# Power_Supply.net
KiCad netlist of a schematic drawn in Altium Designer
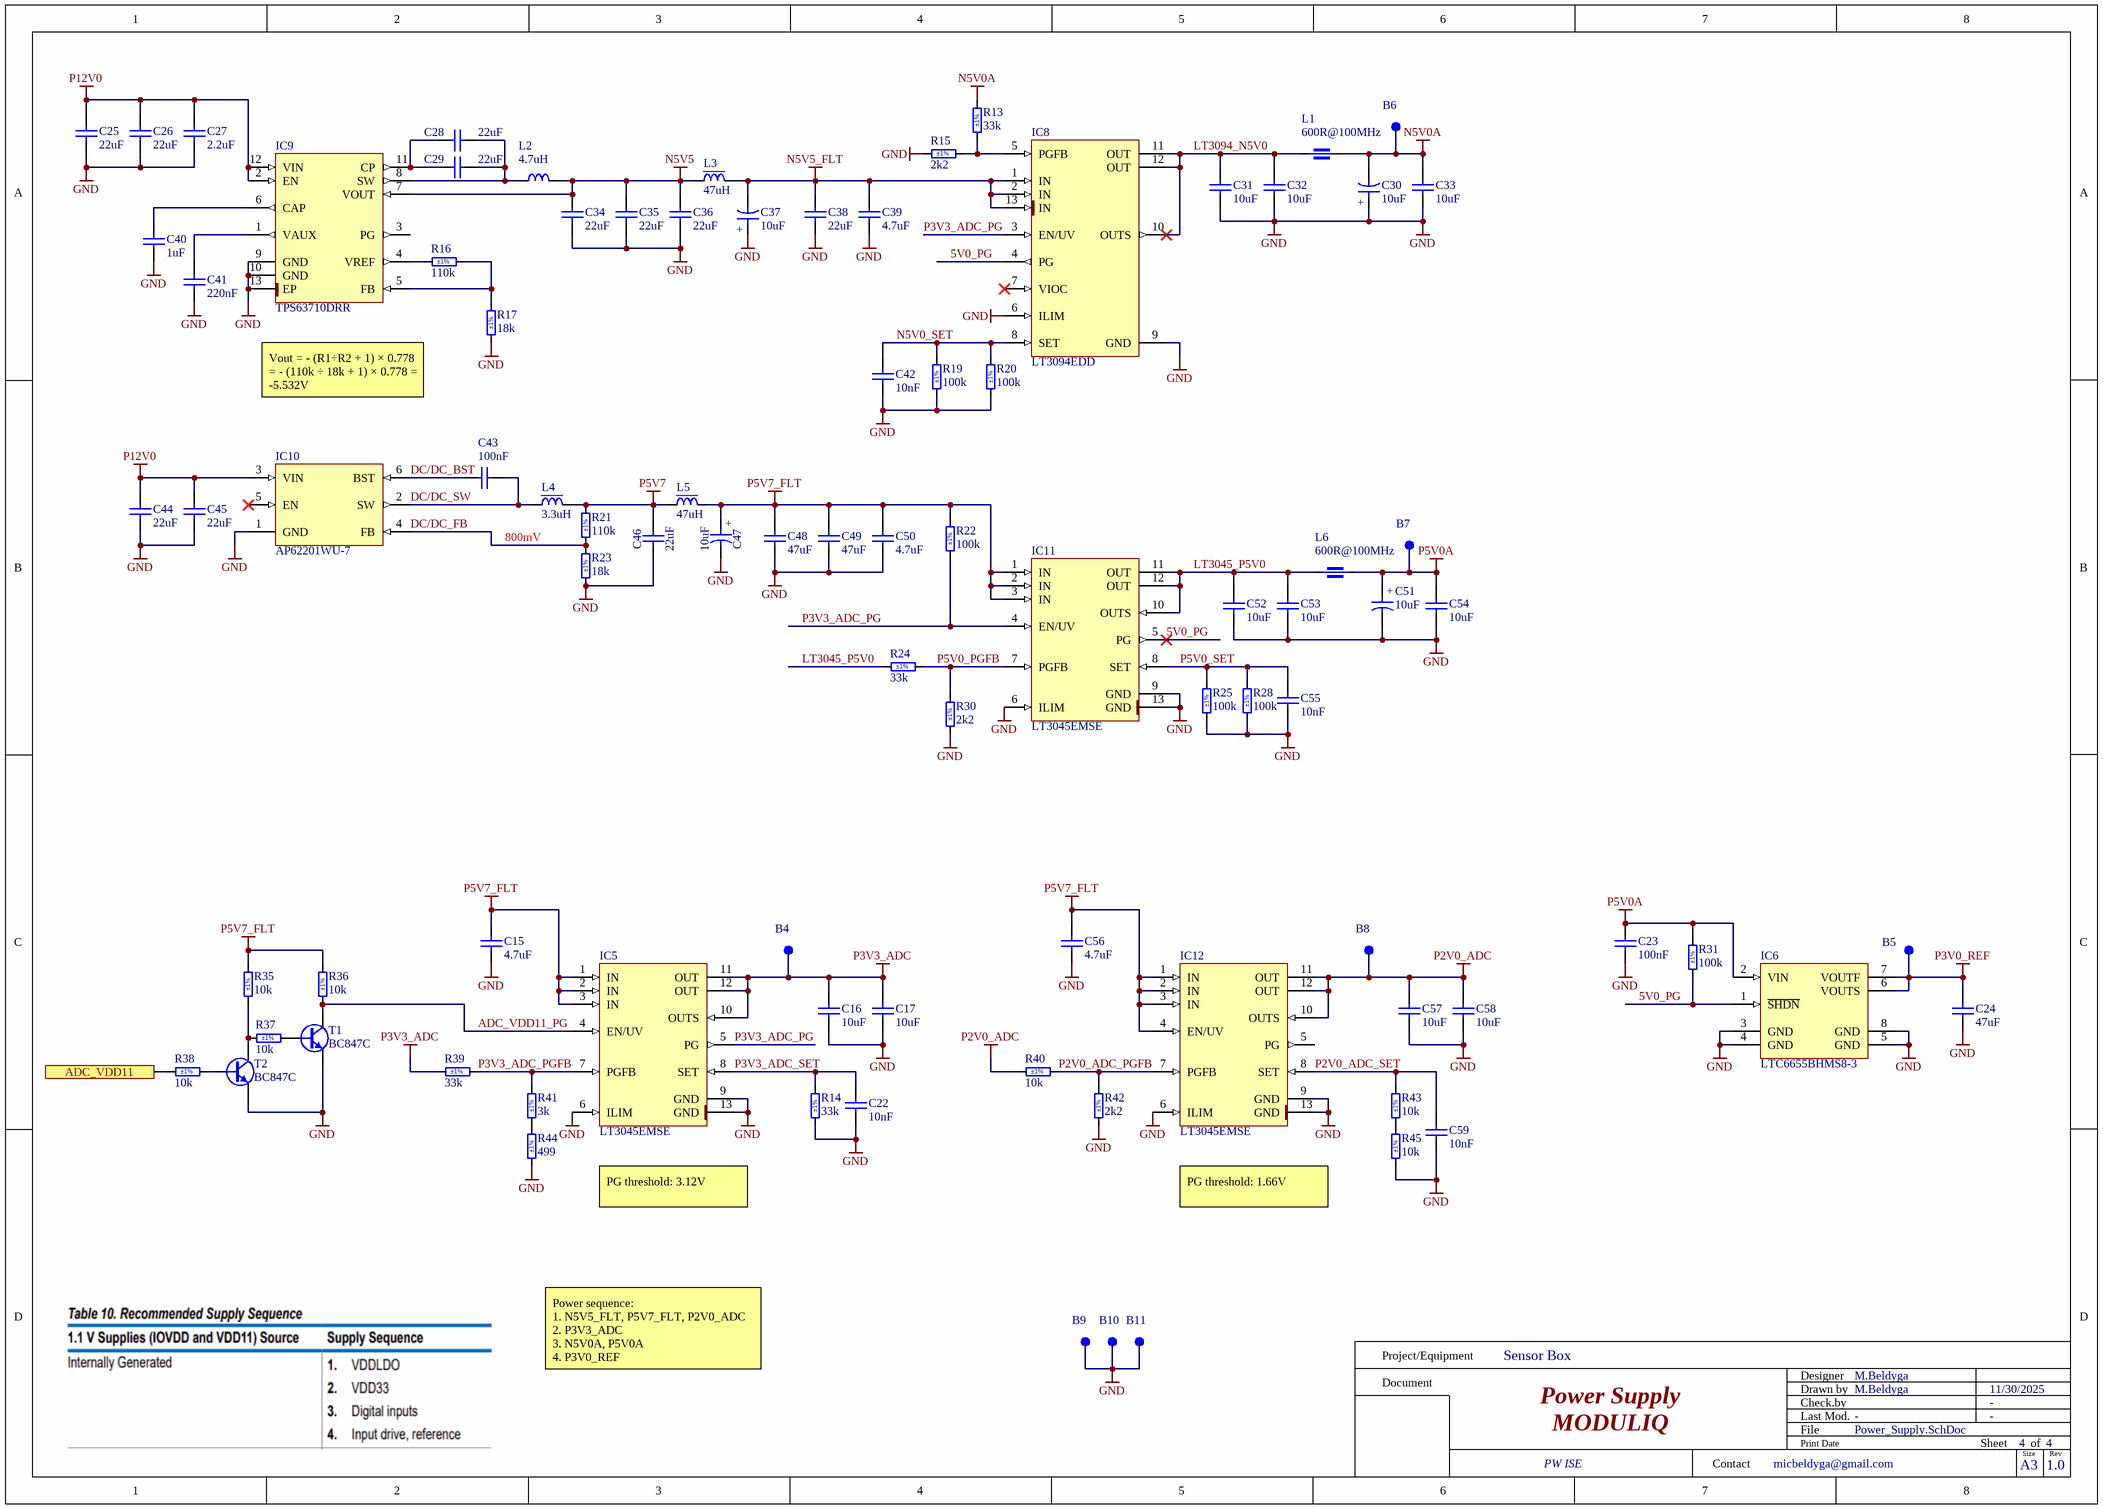
[diagram p0: Power_Supply.SchDoc]

(export (version "E")
  (design (tool "Eeschema 10.0.6"))
  (components
    (comp (ref "B4")
      (value "SMD Pad")
      (footprint "C100")
      (description "Pad")
      (fields (field (name "PART NUMBER") "SMD_PAD_D1MM") (field (name "AUTHOR") "CERN DEM JLC"))
      (libsource (lib "Eletro-mechanical") (part "Single SMD Pad (Round)"))
    )
    (comp (ref "B5")
      (value "SMD Pad")
      (footprint "C100")
      (description "Pad")
      (fields (field (name "PART NUMBER") "SMD_PAD_D1MM") (field (name "AUTHOR") "CERN DEM JLC"))
      (libsource (lib "Eletro-mechanical") (part "Single SMD Pad (Round)"))
    )
    (comp (ref "B6")
      (value "SMD Pad")
      (footprint "C100")
      (description "Pad")
      (fields (field (name "PART NUMBER") "SMD_PAD_D1MM") (field (name "AUTHOR") "CERN DEM JLC"))
      (libsource (lib "Eletro-mechanical") (part "Single SMD Pad (Round)"))
    )
    (comp (ref "B7")
      (value "SMD Pad")
      (footprint "C100")
      (description "Pad")
      (fields (field (name "PART NUMBER") "SMD_PAD_D1MM") (field (name "AUTHOR") "CERN DEM JLC"))
      (libsource (lib "Eletro-mechanical") (part "Single SMD Pad (Round)"))
    )
    (comp (ref "B8")
      (value "SMD Pad")
      (footprint "C100")
      (description "Pad")
      (fields (field (name "PART NUMBER") "SMD_PAD_D1MM") (field (name "AUTHOR") "CERN DEM JLC"))
      (libsource (lib "Eletro-mechanical") (part "Single SMD Pad (Round)"))
    )
    (comp (ref "B9")
      (value "SMD Pad")
      (footprint "C100")
      (description "Pad")
      (fields (field (name "PART NUMBER") "SMD_PAD_D1MM") (field (name "AUTHOR") "CERN DEM JLC"))
      (libsource (lib "Eletro-mechanical") (part "Single SMD Pad (Round)"))
    )
    (comp (ref "B10")
      (value "SMD Pad")
      (footprint "C100")
      (description "Pad")
      (fields (field (name "PART NUMBER") "SMD_PAD_D1MM") (field (name "AUTHOR") "CERN DEM JLC"))
      (libsource (lib "Eletro-mechanical") (part "Single SMD Pad (Round)"))
    )
    (comp (ref "B11")
      (value "SMD Pad")
      (footprint "C100")
      (description "Pad")
      (fields (field (name "PART NUMBER") "SMD_PAD_D1MM") (field (name "AUTHOR") "CERN DEM JLC"))
      (libsource (lib "Eletro-mechanical") (part "Single SMD Pad (Round)"))
    )
    (comp (ref "C15")
      (value "4.7uF")
      (footprint "CAPC1608X90N")
      (description "Non-polarised capacitor")
      (fields
        (field (name "PART NUMBER") "CC0603_4.7UF_25V_10%_X5R")
        (field (name "VOLTAGE") "25V")
        (field (name "AUTHOR") "CERN DEM JLC")
      )
      (libsource (lib "Capacitors") (part "Capacitor - non polarized"))
    )
    (comp (ref "C16")
      (value "10uF")
      (footprint "CAPC2012X95N")
      (description "Non-polarised capacitor")
      (fields
        (field (name "PART NUMBER") "CC0805_10UF_25V_10%_X5R")
        (field (name "VOLTAGE") "25V")
        (field (name "AUTHOR") "CERN DEM JLC")
      )
      (libsource (lib "Capacitors") (part "Capacitor - non polarized"))
    )
    (comp (ref "C17")
      (value "10uF")
      (footprint "CAPC2012X95N")
      (description "Non-polarised capacitor")
      (fields
        (field (name "PART NUMBER") "CC0805_10UF_25V_10%_X5R")
        (field (name "VOLTAGE") "25V")
        (field (name "AUTHOR") "CERN DEM JLC")
      )
      (libsource (lib "Capacitors") (part "Capacitor - non polarized"))
    )
    (comp (ref "C22")
      (value "10nF")
      (footprint "CAPC1005X55N")
      (description "Non-polarised capacitor")
      (fields
        (field (name "PART NUMBER") "CC0402_10NF_16V_10%_X7R")
        (field (name "VOLTAGE") "16V")
        (field (name "AUTHOR") "CERN DEM JLC")
      )
      (libsource (lib "Capacitors") (part "Capacitor - non polarized"))
    )
    (comp (ref "C23")
      (value "100nF")
      (footprint "CAPC1005X55N")
      (description "Non-polarised capacitor")
      (fields
        (field (name "PART NUMBER") "CC0402_100NF_50V_10%_X7R")
        (field (name "VOLTAGE") "50V")
        (field (name "AUTHOR") "CERN DEM MR")
      )
      (libsource (lib "Capacitors") (part "Capacitor - non polarized"))
    )
    (comp (ref "C24")
      (value "47uF")
      (footprint "CAPC2012X140N")
      (description "Non-polarised capacitor")
      (fields
        (field (name "PART NUMBER") "CC0805_47UF_6.3V_10%_X5R")
        (field (name "VOLTAGE") "6.3V")
        (field (name "AUTHOR") "CERN DEM HF")
      )
      (libsource (lib "Capacitors") (part "Capacitor - non polarized"))
    )
    (comp (ref "C25")
      (value "22uF")
      (footprint "CAPC2012X135N")
      (description "Non-polarised capacitor")
      (fields
        (field (name "PART NUMBER") "CC0805_22UF_16V_10%_X5R")
        (field (name "VOLTAGE") "16V")
        (field (name "AUTHOR") "CERN DEM JLC")
      )
      (libsource (lib "Capacitors") (part "Capacitor - non polarized"))
    )
    (comp (ref "C26")
      (value "22uF")
      (footprint "CAPC2012X135N")
      (description "Non-polarised capacitor")
      (fields
        (field (name "PART NUMBER") "CC0805_22UF_16V_10%_X5R")
        (field (name "VOLTAGE") "16V")
        (field (name "AUTHOR") "CERN DEM JLC")
      )
      (libsource (lib "Capacitors") (part "Capacitor - non polarized"))
    )
    (comp (ref "C27")
      (value "2.2uF")
      (footprint "CAPC1005X55N")
      (description "Non-polarised capacitor")
      (fields
        (field (name "PART NUMBER") "CC0402_2.2UF_25V_10%_X5R")
        (field (name "VOLTAGE") "25V")
        (field (name "AUTHOR") "CERN DEM BC")
      )
      (libsource (lib "Capacitors") (part "Capacitor - non polarized"))
    )
    (comp (ref "C28")
      (value "22uF")
      (footprint "CAPC2012X135N")
      (description "Non-polarised capacitor")
      (fields
        (field (name "PART NUMBER") "CC0805_22UF_16V_10%_X5R")
        (field (name "VOLTAGE") "16V")
        (field (name "AUTHOR") "CERN DEM JLC")
      )
      (libsource (lib "Capacitors") (part "Capacitor - non polarized"))
    )
    (comp (ref "C29")
      (value "22uF")
      (footprint "CAPC2012X135N")
      (description "Non-polarised capacitor")
      (fields
        (field (name "PART NUMBER") "CC0805_22UF_16V_10%_X5R")
        (field (name "VOLTAGE") "16V")
        (field (name "AUTHOR") "CERN DEM JLC")
      )
      (libsource (lib "Capacitors") (part "Capacitor - non polarized"))
    )
    (comp (ref "C30")
      (value "10uF")
      (footprint "CAPMP3216X180N")
      (description "Polarised capacitor")
      (fields
        (field (name "PART NUMBER") "CTE3216-18_10UF_10V_10%_LESR1800")
        (field (name "VOLTAGE") "10V")
        (field (name "AUTHOR") "CERN DEM JLC")
      )
      (libsource (lib "Capacitors") (part "Capacitor - polarized"))
    )
    (comp (ref "C31")
      (value "10uF")
      (footprint "CAPC2012X95N")
      (description "Non-polarised capacitor")
      (fields
        (field (name "PART NUMBER") "CC0805_10UF_25V_10%_X5R")
        (field (name "VOLTAGE") "25V")
        (field (name "AUTHOR") "CERN DEM JLC")
      )
      (libsource (lib "Capacitors") (part "Capacitor - non polarized"))
    )
    (comp (ref "C32")
      (value "10uF")
      (footprint "CAPC2012X95N")
      (description "Non-polarised capacitor")
      (fields
        (field (name "PART NUMBER") "CC0805_10UF_25V_10%_X5R")
        (field (name "VOLTAGE") "25V")
        (field (name "AUTHOR") "CERN DEM JLC")
      )
      (libsource (lib "Capacitors") (part "Capacitor - non polarized"))
    )
    (comp (ref "C33")
      (value "10uF")
      (footprint "CAPC2012X95N")
      (description "Non-polarised capacitor")
      (fields
        (field (name "PART NUMBER") "CC0805_10UF_25V_10%_X5R")
        (field (name "VOLTAGE") "25V")
        (field (name "AUTHOR") "CERN DEM JLC")
      )
      (libsource (lib "Capacitors") (part "Capacitor - non polarized"))
    )
    (comp (ref "C34")
      (value "22uF")
      (footprint "CAPC2012X135N")
      (description "Non-polarised capacitor")
      (fields
        (field (name "PART NUMBER") "CC0805_22UF_16V_10%_X5R")
        (field (name "VOLTAGE") "16V")
        (field (name "AUTHOR") "CERN DEM JLC")
      )
      (libsource (lib "Capacitors") (part "Capacitor - non polarized"))
    )
    (comp (ref "C35")
      (value "22uF")
      (footprint "CAPC2012X135N")
      (description "Non-polarised capacitor")
      (fields
        (field (name "PART NUMBER") "CC0805_22UF_16V_10%_X5R")
        (field (name "VOLTAGE") "16V")
        (field (name "AUTHOR") "CERN DEM JLC")
      )
      (libsource (lib "Capacitors") (part "Capacitor - non polarized"))
    )
    (comp (ref "C36")
      (value "22uF")
      (footprint "CAPC2012X135N")
      (description "Non-polarised capacitor")
      (fields
        (field (name "PART NUMBER") "CC0805_22UF_16V_10%_X5R")
        (field (name "VOLTAGE") "16V")
        (field (name "AUTHOR") "CERN DEM JLC")
      )
      (libsource (lib "Capacitors") (part "Capacitor - non polarized"))
    )
    (comp (ref "C37")
      (value "10uF")
      (footprint "CAPMP3216X180N")
      (description "Polarised capacitor")
      (fields
        (field (name "PART NUMBER") "CTE3216-18_10UF_16V_20%_AVX_TCJ")
        (field (name "VOLTAGE") "16V")
        (field (name "AUTHOR") "CERN DEM JLC")
      )
      (libsource (lib "Capacitors") (part "Capacitor - polarized"))
    )
    (comp (ref "C38")
      (value "22uF")
      (footprint "CAPC2012X135N")
      (description "Non-polarised capacitor")
      (fields
        (field (name "PART NUMBER") "CC0805_22UF_16V_10%_X5R")
        (field (name "VOLTAGE") "16V")
        (field (name "AUTHOR") "CERN DEM JLC")
      )
      (libsource (lib "Capacitors") (part "Capacitor - non polarized"))
    )
    (comp (ref "C39")
      (value "4.7uF")
      (footprint "CAPC1608X90N")
      (description "Non-polarised capacitor")
      (fields
        (field (name "PART NUMBER") "CC0603_4.7UF_25V_10%_X5R")
        (field (name "VOLTAGE") "25V")
        (field (name "AUTHOR") "CERN DEM JLC")
      )
      (libsource (lib "Capacitors") (part "Capacitor - non polarized"))
    )
    (comp (ref "C40")
      (value "1uF")
      (footprint "CAPC1005X55N")
      (description "Non-polarised capacitor")
      (fields
        (field (name "PART NUMBER") "CC0402_1UF_16V_10%_X5R")
        (field (name "VOLTAGE") "16V")
        (field (name "AUTHOR") "CERN DEM JLC")
      )
      (libsource (lib "Capacitors") (part "Capacitor - non polarized"))
    )
    (comp (ref "C41")
      (value "220nF")
      (footprint "CAPC1005X55N")
      (description "Non-polarised capacitor")
      (fields
        (field (name "PART NUMBER") "CC0402_220NF_25V_10%_X7R")
        (field (name "VOLTAGE") "25V")
        (field (name "AUTHOR") "CERN DEM BC")
      )
      (libsource (lib "Capacitors") (part "Capacitor - non polarized"))
    )
    (comp (ref "C42")
      (value "10nF")
      (footprint "CAPC1005X55N")
      (description "Non-polarised capacitor")
      (fields
        (field (name "PART NUMBER") "CC0402_10NF_16V_10%_X7R")
        (field (name "VOLTAGE") "16V")
        (field (name "AUTHOR") "CERN DEM JLC")
      )
      (libsource (lib "Capacitors") (part "Capacitor - non polarized"))
    )
    (comp (ref "C43")
      (value "100nF")
      (footprint "CAPC1005X55N")
      (description "Non-polarised capacitor")
      (fields
        (field (name "PART NUMBER") "CC0402_100NF_16V_10%_X7R")
        (field (name "VOLTAGE") "16V")
        (field (name "AUTHOR") "CERN DEM JLC")
      )
      (libsource (lib "Capacitors") (part "Capacitor - non polarized"))
    )
    (comp (ref "C44")
      (value "22uF")
      (footprint "CAPC2012X135N")
      (description "Non-polarised capacitor")
      (fields
        (field (name "PART NUMBER") "CC0805_22UF_16V_10%_X5R")
        (field (name "VOLTAGE") "16V")
        (field (name "AUTHOR") "CERN DEM JLC")
      )
      (libsource (lib "Capacitors") (part "Capacitor - non polarized"))
    )
    (comp (ref "C45")
      (value "22uF")
      (footprint "CAPC2012X135N")
      (description "Non-polarised capacitor")
      (fields
        (field (name "PART NUMBER") "CC0805_22UF_16V_10%_X5R")
        (field (name "VOLTAGE") "16V")
        (field (name "AUTHOR") "CERN DEM JLC")
      )
      (libsource (lib "Capacitors") (part "Capacitor - non polarized"))
    )
    (comp (ref "C46")
      (value "22uF")
      (footprint "CAPC2012X135N")
      (description "Non-polarised capacitor")
      (fields
        (field (name "PART NUMBER") "CC0805_22UF_16V_10%_X5R")
        (field (name "VOLTAGE") "16V")
        (field (name "AUTHOR") "CERN DEM JLC")
      )
      (libsource (lib "Capacitors") (part "Capacitor - non polarized"))
    )
    (comp (ref "C47")
      (value "10uF")
      (footprint "CAPMP3216X180N")
      (description "Polarised capacitor")
      (fields
        (field (name "PART NUMBER") "CTE3216-18_10UF_16V_20%_AVX_TCJ")
        (field (name "VOLTAGE") "16V")
        (field (name "AUTHOR") "CERN DEM JLC")
      )
      (libsource (lib "Capacitors") (part "Capacitor - polarized"))
    )
    (comp (ref "C48")
      (value "47uF")
      (footprint "CAPC3216X180N")
      (description "Non-polarised capacitor")
      (fields
        (field (name "PART NUMBER") "CC1206_47UF_25V_20%_X5R")
        (field (name "VOLTAGE") "25V")
        (field (name "AUTHOR") "CERN DEM JLC")
      )
      (libsource (lib "Capacitors") (part "Capacitor - non polarized"))
    )
    (comp (ref "C49")
      (value "47uF")
      (footprint "CAPC3216X180N")
      (description "Non-polarised capacitor")
      (fields
        (field (name "PART NUMBER") "CC1206_47UF_25V_20%_X5R")
        (field (name "VOLTAGE") "25V")
        (field (name "AUTHOR") "CERN DEM JLC")
      )
      (libsource (lib "Capacitors") (part "Capacitor - non polarized"))
    )
    (comp (ref "C50")
      (value "4.7uF")
      (footprint "CAPC1608X90N")
      (description "Non-polarised capacitor")
      (fields
        (field (name "PART NUMBER") "CC0603_4.7UF_25V_10%_X5R")
        (field (name "VOLTAGE") "25V")
        (field (name "AUTHOR") "CERN DEM JLC")
      )
      (libsource (lib "Capacitors") (part "Capacitor - non polarized"))
    )
    (comp (ref "C51")
      (value "10uF")
      (footprint "CAPMP3216X180N")
      (description "Polarised capacitor")
      (fields
        (field (name "PART NUMBER") "CTE3216-18_10UF_10V_10%_LESR1800")
        (field (name "VOLTAGE") "10V")
        (field (name "AUTHOR") "CERN DEM JLC")
      )
      (libsource (lib "Capacitors") (part "Capacitor - polarized"))
    )
    (comp (ref "C52")
      (value "10uF")
      (footprint "CAPC2012X95N")
      (description "Non-polarised capacitor")
      (fields
        (field (name "PART NUMBER") "CC0805_10UF_25V_10%_X5R")
        (field (name "VOLTAGE") "25V")
        (field (name "AUTHOR") "CERN DEM JLC")
      )
      (libsource (lib "Capacitors") (part "Capacitor - non polarized"))
    )
    (comp (ref "C53")
      (value "10uF")
      (footprint "CAPC2012X95N")
      (description "Non-polarised capacitor")
      (fields
        (field (name "PART NUMBER") "CC0805_10UF_25V_10%_X5R")
        (field (name "VOLTAGE") "25V")
        (field (name "AUTHOR") "CERN DEM JLC")
      )
      (libsource (lib "Capacitors") (part "Capacitor - non polarized"))
    )
    (comp (ref "C54")
      (value "10uF")
      (footprint "CAPC2012X95N")
      (description "Non-polarised capacitor")
      (fields
        (field (name "PART NUMBER") "CC0805_10UF_25V_10%_X5R")
        (field (name "VOLTAGE") "25V")
        (field (name "AUTHOR") "CERN DEM JLC")
      )
      (libsource (lib "Capacitors") (part "Capacitor - non polarized"))
    )
    (comp (ref "C55")
      (value "10nF")
      (footprint "CAPC1005X55N")
      (description "Non-polarised capacitor")
      (fields
        (field (name "PART NUMBER") "CC0402_10NF_16V_10%_X7R")
        (field (name "VOLTAGE") "16V")
        (field (name "AUTHOR") "CERN DEM JLC")
      )
      (libsource (lib "Capacitors") (part "Capacitor - non polarized"))
    )
    (comp (ref "C56")
      (value "4.7uF")
      (footprint "CAPC1608X90N")
      (description "Non-polarised capacitor")
      (fields
        (field (name "PART NUMBER") "CC0603_4.7UF_25V_10%_X5R")
        (field (name "VOLTAGE") "25V")
        (field (name "AUTHOR") "CERN DEM JLC")
      )
      (libsource (lib "Capacitors") (part "Capacitor - non polarized"))
    )
    (comp (ref "C57")
      (value "10uF")
      (footprint "CAPC2012X95N")
      (description "Non-polarised capacitor")
      (fields
        (field (name "PART NUMBER") "CC0805_10UF_25V_10%_X5R")
        (field (name "VOLTAGE") "25V")
        (field (name "AUTHOR") "CERN DEM JLC")
      )
      (libsource (lib "Capacitors") (part "Capacitor - non polarized"))
    )
    (comp (ref "C58")
      (value "10uF")
      (footprint "CAPC2012X95N")
      (description "Non-polarised capacitor")
      (fields
        (field (name "PART NUMBER") "CC0805_10UF_25V_10%_X5R")
        (field (name "VOLTAGE") "25V")
        (field (name "AUTHOR") "CERN DEM JLC")
      )
      (libsource (lib "Capacitors") (part "Capacitor - non polarized"))
    )
    (comp (ref "C59")
      (value "10nF")
      (footprint "CAPC1005X55N")
      (description "Non-polarised capacitor")
      (fields
        (field (name "PART NUMBER") "CC0402_10NF_16V_10%_X7R")
        (field (name "VOLTAGE") "16V")
        (field (name "AUTHOR") "CERN DEM JLC")
      )
      (libsource (lib "Capacitors") (part "Capacitor - non polarized"))
    )
    (comp (ref "IC5")
      (value "LT3045EMSE")
      (footprint "SOP65P490X110-13N-R175X294")
      (description "20V, 500mA, Ultralow Noise, Ultrahigh PSRR Linear Regulator")
      (fields (field (name "MANUFACTURER") "LINEAR TECHNOLOGY") (field (name "AUTHOR") "CERN DEM HF"))
      (libsource (lib "ICs And Semiconductors") (part "LT3045"))
    )
    (comp (ref "IC6")
      (value "LTC6655BHMS8-3")
      (footprint "SOP65P490X110-8N")
      (description "0.25ppm Noise, Low Drift Precision Buffered Voltage Reference")
      (fields (field (name "MANUFACTURER") "ANALOG DEVICES") (field (name "AUTHOR") "CERN DEM HF"))
      (libsource (lib "ICs And Semiconductors") (part "LTC6655"))
    )
    (comp (ref "IC8")
      (value "LT3094EDD")
      (footprint "SON45P300X300X80-13N-R175X248")
      (description "-20V, 500mA, Ultralow Noise, Ultrahigh PSRR Negative Linear Regulator")
      (fields
        (field (name "PART NUMBER") "LT3094EDD#PBF")
        (field (name "MANUFACTURER") "LINEAR TECHNOLOGY")
        (field (name "AUTHOR") "CERN DEM JLC")
      )
      (libsource (lib "ICs And Semiconductors") (part "LT3094"))
    )
    (comp (ref "IC9")
      (value "TPS63710DRR")
      (footprint "SON50P300X300X80-13N-R160X260")
      (description "-1 to -5.5VDC, 1A Output, Low Noise Synchronous Inverting Buck Converter")
      (fields (field (name "MANUFACTURER") "TEXAS INSTRUMENTS") (field (name "AUTHOR") "CERN DEM BC"))
      (libsource (lib "ICs And Semiconductors") (part "TPS63710"))
    )
    (comp (ref "IC10")
      (value "AP62201WU-7")
      (footprint "SOT95P280X100-6N")
      (description "4.2V TO 18V INPUT, 2A LOW IQ SYNCHRONOUS BUCK CONVERTER")
      (fields
        (field (name "MANUFACTURER") "DIODES INCORPORATED")
        (field (name "MANUFACTURER PART NUMBER") "AP62201WU")
        (field (name "AUTHOR") "CERN DEM HF")
      )
      (libsource (lib "ICs And Semiconductors") (part "AP62201WU"))
    )
    (comp (ref "IC11")
      (value "LT3045EMSE")
      (footprint "SOP65P490X110-13N-R175X294")
      (description "20V, 500mA, Ultralow Noise, Ultrahigh PSRR Linear Regulator")
      (fields (field (name "MANUFACTURER") "LINEAR TECHNOLOGY") (field (name "AUTHOR") "CERN DEM HF"))
      (libsource (lib "ICs And Semiconductors") (part "LT3045"))
    )
    (comp (ref "IC12")
      (value "LT3045EMSE")
      (footprint "SOP65P490X110-13N-R175X294")
      (description "20V, 500mA, Ultralow Noise, Ultrahigh PSRR Linear Regulator")
      (fields (field (name "MANUFACTURER") "LINEAR TECHNOLOGY") (field (name "AUTHOR") "CERN DEM HF"))
      (libsource (lib "ICs And Semiconductors") (part "LT3045"))
    )
    (comp (ref "L1")
      (value "600R@100MHz")
      (footprint "INDC1608X95N")
      (fields
        (field (name "PART NUMBER") "IND0603_MURATA_BLM18BD601SN1D")
        (field (name "POWER") "200mA")
        (field (name "TOLERANCE") "±25%")
        (field (name "AUTHOR") "CERN DEM JLC")
      )
      (libsource (lib "Inductors & Transformers") (part "Ferrite Bead"))
    )
    (comp (ref "L2")
      (value "4.7uH")
      (footprint "IND_COILCRAFT_EPL3015")
      (description "Inductor")
      (fields
        (field (name "PART NUMBER") "IND_4.7UH_20%_COILCRAFT_EPL3015")
        (field (name "POWER") "1A")
        (field (name "AUTHOR") "CERN DEM BC")
      )
      (libsource (lib "Inductors & Transformers") (part "Inductor"))
    )
    (comp (ref "L3")
      (value "47uH")
      (footprint "IND_WURTH_WE-LHMI_7050")
      (description "Inductor With Core")
      (fields
        (field (name "PART NUMBER") "IND_47UH_20%_WURTH_WE-LHMI_74437349470")
        (field (name "POWER") "1.45A")
        (field (name "AUTHOR") "CERN DEM HF")
      )
      (libsource (lib "Inductors & Transformers") (part "Inductor With Magnetic core"))
    )
    (comp (ref "L4")
      (value "3.3uH")
      (footprint "IND_COILCRAFT_SD43")
      (description "Inductor With Core")
      (fields
        (field (name "PART NUMBER") "IND_3.3UH_20%_COILCRAFT_SD43-332MLB")
        (field (name "POWER") "2.1A")
        (field (name "AUTHOR") "CERN DEM JLC")
      )
      (libsource (lib "Inductors & Transformers") (part "Inductor With Magnetic core"))
    )
    (comp (ref "L5")
      (value "47uH")
      (footprint "IND_WURTH_WE-LHMI_7050")
      (description "Inductor With Core")
      (fields
        (field (name "PART NUMBER") "IND_47UH_20%_WURTH_WE-LHMI_74437349470")
        (field (name "POWER") "1.45A")
        (field (name "AUTHOR") "CERN DEM HF")
      )
      (libsource (lib "Inductors & Transformers") (part "Inductor With Magnetic core"))
    )
    (comp (ref "L6")
      (value "600R@100MHz")
      (footprint "INDC1608X95N")
      (fields
        (field (name "PART NUMBER") "IND0603_MURATA_BLM18BD601SN1D")
        (field (name "POWER") "200mA")
        (field (name "TOLERANCE") "±25%")
        (field (name "AUTHOR") "CERN DEM JLC")
      )
      (libsource (lib "Inductors & Transformers") (part "Ferrite Bead"))
    )
    (comp (ref "R13")
      (value "33k")
      (footprint "RESC1005X40N")
      (description "Resistor - 1%")
      (fields
        (field (name "TOLERANCE") "±1%")
        (field (name "PART NUMBER") "R0402_33K_1%_0.0625W_100PPM")
        (field (name "POWER") "0.0625W")
        (field (name "AUTHOR") "CERN DEM JLC")
      )
      (libsource (lib "Resistors") (part "Resistor - 1%"))
    )
    (comp (ref "R14")
      (value "33k")
      (footprint "RESC1005X40N")
      (description "Resistor - 1%")
      (fields
        (field (name "TOLERANCE") "±1%")
        (field (name "PART NUMBER") "R0402_33K_1%_0.0625W_100PPM")
        (field (name "POWER") "0.0625W")
        (field (name "AUTHOR") "CERN DEM JLC")
      )
      (libsource (lib "Resistors") (part "Resistor - 1%"))
    )
    (comp (ref "R15")
      (value "2k2")
      (footprint "RESC1005X40N")
      (description "Resistor - 1%")
      (fields
        (field (name "TOLERANCE") "±1%")
        (field (name "PART NUMBER") "R0402_2K2_1%_0.0625W_100PPM")
        (field (name "POWER") "0.0625W")
        (field (name "AUTHOR") "CERN DEM JLC")
      )
      (libsource (lib "Resistors") (part "Resistor - 1%"))
    )
    (comp (ref "R16")
      (value "110k")
      (footprint "RESC1005X40N")
      (description "Resistor - 1%")
      (fields
        (field (name "TOLERANCE") "±1%")
        (field (name "PART NUMBER") "R0402_110K_1%_0.0625W_100PPM")
        (field (name "POWER") "0.0625W")
        (field (name "AUTHOR") "CERN DEM JLC")
      )
      (libsource (lib "Resistors") (part "Resistor - 1%"))
    )
    (comp (ref "R17")
      (value "18k")
      (footprint "RESC1005X40N")
      (description "Resistor - 1%")
      (fields
        (field (name "TOLERANCE") "±1%")
        (field (name "PART NUMBER") "R0402_18K_1%_0.0625W_100PPM")
        (field (name "POWER") "0.0625W")
        (field (name "AUTHOR") "CERN DEM JLC")
      )
      (libsource (lib "Resistors") (part "Resistor - 1%"))
    )
    (comp (ref "R19")
      (value "100k")
      (footprint "RESC1005X40N")
      (description "Resistor - 1%")
      (fields
        (field (name "TOLERANCE") "±1%")
        (field (name "PART NUMBER") "R0402_100K_1%_0.0625W_100PPM")
        (field (name "POWER") "0.0625W")
        (field (name "AUTHOR") "CERN DEM JLC")
      )
      (libsource (lib "Resistors") (part "Resistor - 1%"))
    )
    (comp (ref "R20")
      (value "100k")
      (footprint "RESC1005X40N")
      (description "Resistor - 1%")
      (fields
        (field (name "TOLERANCE") "±1%")
        (field (name "PART NUMBER") "R0402_100K_1%_0.0625W_100PPM")
        (field (name "POWER") "0.0625W")
        (field (name "AUTHOR") "CERN DEM JLC")
      )
      (libsource (lib "Resistors") (part "Resistor - 1%"))
    )
    (comp (ref "R21")
      (value "110k")
      (footprint "RESC1005X40N")
      (description "Resistor - 1%")
      (fields
        (field (name "TOLERANCE") "±1%")
        (field (name "PART NUMBER") "R0402_110K_1%_0.0625W_100PPM")
        (field (name "POWER") "0.0625W")
        (field (name "AUTHOR") "CERN DEM JLC")
      )
      (libsource (lib "Resistors") (part "Resistor - 1%"))
    )
    (comp (ref "R22")
      (value "100k")
      (footprint "RESC1005X40N")
      (description "Resistor - 1%")
      (fields
        (field (name "TOLERANCE") "±1%")
        (field (name "PART NUMBER") "R0402_100K_1%_0.0625W_100PPM")
        (field (name "POWER") "0.0625W")
        (field (name "AUTHOR") "CERN DEM JLC")
      )
      (libsource (lib "Resistors") (part "Resistor - 1%"))
    )
    (comp (ref "R23")
      (value "18k")
      (footprint "RESC1005X40N")
      (description "Resistor - 1%")
      (fields
        (field (name "TOLERANCE") "±1%")
        (field (name "PART NUMBER") "R0402_18K_1%_0.0625W_100PPM")
        (field (name "POWER") "0.0625W")
        (field (name "AUTHOR") "CERN DEM JLC")
      )
      (libsource (lib "Resistors") (part "Resistor - 1%"))
    )
    (comp (ref "R24")
      (value "33k")
      (footprint "RESC1005X40N")
      (description "Resistor - 1%")
      (fields
        (field (name "TOLERANCE") "±1%")
        (field (name "PART NUMBER") "R0402_33K_1%_0.0625W_100PPM")
        (field (name "POWER") "0.0625W")
        (field (name "AUTHOR") "CERN DEM JLC")
      )
      (libsource (lib "Resistors") (part "Resistor - 1%"))
    )
    (comp (ref "R25")
      (value "100k")
      (footprint "RESC1005X40N")
      (description "Resistor - 1%")
      (fields
        (field (name "TOLERANCE") "±1%")
        (field (name "PART NUMBER") "R0402_100K_1%_0.0625W_100PPM")
        (field (name "POWER") "0.0625W")
        (field (name "AUTHOR") "CERN DEM JLC")
      )
      (libsource (lib "Resistors") (part "Resistor - 1%"))
    )
    (comp (ref "R28")
      (value "100k")
      (footprint "RESC1005X40N")
      (description "Resistor - 1%")
      (fields
        (field (name "TOLERANCE") "±1%")
        (field (name "PART NUMBER") "R0402_100K_1%_0.0625W_100PPM")
        (field (name "POWER") "0.0625W")
        (field (name "AUTHOR") "CERN DEM JLC")
      )
      (libsource (lib "Resistors") (part "Resistor - 1%"))
    )
    (comp (ref "R30")
      (value "2k2")
      (footprint "RESC1005X40N")
      (description "Resistor - 1%")
      (fields
        (field (name "TOLERANCE") "±1%")
        (field (name "PART NUMBER") "R0402_2K2_1%_0.0625W_100PPM")
        (field (name "POWER") "0.0625W")
        (field (name "AUTHOR") "CERN DEM JLC")
      )
      (libsource (lib "Resistors") (part "Resistor - 1%"))
    )
    (comp (ref "R31")
      (value "100k")
      (footprint "RESC1005X40N")
      (description "Resistor - 1%")
      (fields
        (field (name "TOLERANCE") "±1%")
        (field (name "PART NUMBER") "R0402_100K_1%_0.0625W_100PPM")
        (field (name "POWER") "0.0625W")
        (field (name "AUTHOR") "CERN DEM JLC")
      )
      (libsource (lib "Resistors") (part "Resistor - 1%"))
    )
    (comp (ref "R35")
      (value "10k")
      (footprint "RESC1005X40N")
      (description "Resistor - 1%")
      (fields
        (field (name "TOLERANCE") "±1%")
        (field (name "PART NUMBER") "R0402_10K_1%_0.0625W_100PPM")
        (field (name "POWER") "0.0625W")
        (field (name "AUTHOR") "CERN DEM JLC")
      )
      (libsource (lib "Resistors") (part "Resistor - 1%"))
    )
    (comp (ref "R36")
      (value "10k")
      (footprint "RESC1005X40N")
      (description "Resistor - 1%")
      (fields
        (field (name "TOLERANCE") "±1%")
        (field (name "PART NUMBER") "R0402_10K_1%_0.0625W_100PPM")
        (field (name "POWER") "0.0625W")
        (field (name "AUTHOR") "CERN DEM JLC")
      )
      (libsource (lib "Resistors") (part "Resistor - 1%"))
    )
    (comp (ref "R37")
      (value "10k")
      (footprint "RESC1005X40N")
      (description "Resistor - 1%")
      (fields
        (field (name "TOLERANCE") "±1%")
        (field (name "PART NUMBER") "R0402_10K_1%_0.0625W_100PPM")
        (field (name "POWER") "0.0625W")
        (field (name "AUTHOR") "CERN DEM JLC")
      )
      (libsource (lib "Resistors") (part "Resistor - 1%"))
    )
    (comp (ref "R38")
      (value "10k")
      (footprint "RESC1005X40N")
      (description "Resistor - 1%")
      (fields
        (field (name "TOLERANCE") "±1%")
        (field (name "PART NUMBER") "R0402_10K_1%_0.0625W_100PPM")
        (field (name "POWER") "0.0625W")
        (field (name "AUTHOR") "CERN DEM JLC")
      )
      (libsource (lib "Resistors") (part "Resistor - 1%"))
    )
    (comp (ref "R39")
      (value "33k")
      (footprint "RESC1005X40N")
      (description "Resistor - 1%")
      (fields
        (field (name "TOLERANCE") "±1%")
        (field (name "PART NUMBER") "R0402_33K_1%_0.0625W_100PPM")
        (field (name "POWER") "0.0625W")
        (field (name "AUTHOR") "CERN DEM JLC")
      )
      (libsource (lib "Resistors") (part "Resistor - 1%"))
    )
    (comp (ref "R40")
      (value "10k")
      (footprint "RESC1005X40N")
      (description "Resistor - 1%")
      (fields
        (field (name "TOLERANCE") "±1%")
        (field (name "PART NUMBER") "R0402_10K_1%_0.0625W_100PPM")
        (field (name "POWER") "0.0625W")
        (field (name "AUTHOR") "CERN DEM JLC")
      )
      (libsource (lib "Resistors") (part "Resistor - 1%"))
    )
    (comp (ref "R41")
      (value "3k")
      (footprint "RESC1005X40N")
      (description "Resistor - 1%")
      (fields
        (field (name "TOLERANCE") "±1%")
        (field (name "PART NUMBER") "R0402_3K_1%_0.0625W_100PPM")
        (field (name "POWER") "0.0625W")
        (field (name "AUTHOR") "CERN DEM JLC")
      )
      (libsource (lib "Resistors") (part "Resistor - 1%"))
    )
    (comp (ref "R42")
      (value "2k2")
      (footprint "RESC1005X40N")
      (description "Resistor - 1%")
      (fields
        (field (name "TOLERANCE") "±1%")
        (field (name "PART NUMBER") "R0402_2K2_1%_0.0625W_100PPM")
        (field (name "POWER") "0.0625W")
        (field (name "AUTHOR") "CERN DEM JLC")
      )
      (libsource (lib "Resistors") (part "Resistor - 1%"))
    )
    (comp (ref "R43")
      (value "10k")
      (footprint "RESC1005X40N")
      (description "Resistor - 1%")
      (fields
        (field (name "TOLERANCE") "±1%")
        (field (name "PART NUMBER") "R0402_10K_1%_0.0625W_100PPM")
        (field (name "POWER") "0.0625W")
        (field (name "AUTHOR") "CERN DEM JLC")
      )
      (libsource (lib "Resistors") (part "Resistor - 1%"))
    )
    (comp (ref "R44")
      (value "499")
      (footprint "RESC1005X40N")
      (description "Resistor - 1%")
      (fields
        (field (name "TOLERANCE") "±1%")
        (field (name "PART NUMBER") "R0402_499R_1%_0.1W_100PPM")
        (field (name "POWER") "0.1W")
        (field (name "AUTHOR") "CERN DEM MR")
      )
      (libsource (lib "Resistors") (part "Resistor - 1%"))
    )
    (comp (ref "R45")
      (value "10k")
      (footprint "RESC1005X40N")
      (description "Resistor - 1%")
      (fields
        (field (name "TOLERANCE") "±1%")
        (field (name "PART NUMBER") "R0402_10K_1%_0.0625W_100PPM")
        (field (name "POWER") "0.0625W")
        (field (name "AUTHOR") "CERN DEM JLC")
      )
      (libsource (lib "Resistors") (part "Resistor - 1%"))
    )
    (comp (ref "T1")
      (value "BC847C")
      (footprint "SOT95P240X110-3N")
      (description "NPN Transistor")
      (fields (field (name "MANUFACTURER") "INFINEON") (field (name "AUTHOR") "CERN DEM JLC"))
      (libsource (lib "ICs And Semiconductors") (part "NPN B1 E2 C3"))
    )
    (comp (ref "T2")
      (value "BC847C")
      (footprint "SOT95P240X110-3N")
      (description "NPN Transistor")
      (fields (field (name "MANUFACTURER") "INFINEON") (field (name "AUTHOR") "CERN DEM JLC"))
      (libsource (lib "ICs And Semiconductors") (part "NPN B1 E2 C3"))
    )
  )
  (nets
    (net (code "1") (name "/5V0_PG") (class "Default")
      (node (ref "IC11") (pin "5") (pinfunction "PG_5") (pintype "output"))
      (node (ref "IC6") (pin "1") (pinfunction "~{SHDN}_1") (pintype "input"))
      (node (ref "IC8") (pin "4") (pinfunction "PG_4") (pintype "output"))
      (node (ref "R31") (pin "1") (pinfunction "1_1") (pintype "passive"))
    )
    (net (code "2") (name "/ADC_VDD11") (class "Default")
      (node (ref "R38") (pin "2") (pinfunction "2_2") (pintype "passive"))
    )
    (net (code "3") (name "/ADC_VDD11_PG") (class "Default")
      (node (ref "IC5") (pin "4") (pinfunction "EN/UV_4") (pintype "input"))
      (node (ref "R36") (pin "2") (pinfunction "2_2") (pintype "passive"))
      (node (ref "T1") (pin "3") (pinfunction "C_3") (pintype "passive"))
    )
    (net (code "4") (name "/DC{slash}DC_BST") (class "Default")
      (node (ref "C43") (pin "1") (pinfunction "1_1") (pintype "passive"))
      (node (ref "IC10") (pin "6") (pinfunction "BST_6") (pintype "input"))
    )
    (net (code "5") (name "/DC{slash}DC_FB") (class "Default")
      (node (ref "IC10") (pin "4") (pinfunction "FB_4") (pintype "input"))
      (node (ref "R21") (pin "1") (pinfunction "1_1") (pintype "passive"))
      (node (ref "R23") (pin "2") (pinfunction "2_2") (pintype "passive"))
    )
    (net (code "6") (name "/DC{slash}DC_SW") (class "Default")
      (node (ref "C43") (pin "2") (pinfunction "2_2") (pintype "passive"))
      (node (ref "IC10") (pin "2") (pinfunction "SW_2") (pintype "output"))
      (node (ref "L4") (pin "1") (pinfunction "1_1") (pintype "passive"))
    )
    (net (code "7") (name "/LT3045_P5V0") (class "Default")
      (node (ref "C52") (pin "2") (pinfunction "2_2") (pintype "passive"))
      (node (ref "C53") (pin "2") (pinfunction "2_2") (pintype "passive"))
      (node (ref "IC11") (pin "10") (pinfunction "OUTS_10") (pintype "input"))
      (node (ref "IC11") (pin "11") (pinfunction "OUT_11") (pintype "power_in"))
      (node (ref "IC11") (pin "12") (pinfunction "OUT_12") (pintype "power_in"))
      (node (ref "L6") (pin "1") (pinfunction "1_1") (pintype "passive"))
      (node (ref "R24") (pin "2") (pinfunction "2_2") (pintype "passive"))
    )
    (net (code "8") (name "/LT3094_N5V0") (class "Default")
      (node (ref "C31") (pin "2") (pinfunction "2_2") (pintype "passive"))
      (node (ref "C32") (pin "2") (pinfunction "2_2") (pintype "passive"))
      (node (ref "IC8") (pin "10") (pinfunction "OUTS_10") (pintype "output"))
      (node (ref "IC8") (pin "11") (pinfunction "OUT_11") (pintype "power_in"))
      (node (ref "IC8") (pin "12") (pinfunction "OUT_12") (pintype "power_in"))
      (node (ref "L1") (pin "1") (pinfunction "1_1") (pintype "passive"))
    )
    (net (code "9") (name "/N5V0_SET") (class "Default")
      (node (ref "C42") (pin "2") (pinfunction "2_2") (pintype "passive"))
      (node (ref "IC8") (pin "8") (pinfunction "SET_8") (pintype "input"))
      (node (ref "R19") (pin "2") (pinfunction "2_2") (pintype "passive"))
      (node (ref "R20") (pin "2") (pinfunction "2_2") (pintype "passive"))
    )
    (net (code "10") (name "/P2V0_ADC_PGFB") (class "Default")
      (node (ref "IC12") (pin "7") (pinfunction "PGFB_7") (pintype "input"))
      (node (ref "R40") (pin "1") (pinfunction "1_1") (pintype "passive"))
      (node (ref "R42") (pin "1") (pinfunction "1_1") (pintype "passive"))
    )
    (net (code "11") (name "/P2V0_ADC_SET") (class "Default")
      (node (ref "C59") (pin "2") (pinfunction "2_2") (pintype "passive"))
      (node (ref "IC12") (pin "8") (pinfunction "SET_8") (pintype "input"))
      (node (ref "R43") (pin "2") (pinfunction "2_2") (pintype "passive"))
    )
    (net (code "12") (name "/P3V3_ADC_PG") (class "Default")
      (node (ref "IC11") (pin "4") (pinfunction "EN/UV_4") (pintype "input"))
      (node (ref "IC5") (pin "5") (pinfunction "PG_5") (pintype "output"))
      (node (ref "IC8") (pin "3") (pinfunction "EN/UV_3") (pintype "input"))
      (node (ref "R22") (pin "1") (pinfunction "1_1") (pintype "passive"))
    )
    (net (code "13") (name "/P3V3_ADC_PGFB") (class "Default")
      (node (ref "IC5") (pin "7") (pinfunction "PGFB_7") (pintype "input"))
      (node (ref "R39") (pin "1") (pinfunction "1_1") (pintype "passive"))
      (node (ref "R41") (pin "2") (pinfunction "2_2") (pintype "passive"))
    )
    (net (code "14") (name "/P3V3_ADC_SET") (class "Default")
      (node (ref "C22") (pin "2") (pinfunction "2_2") (pintype "passive"))
      (node (ref "IC5") (pin "8") (pinfunction "SET_8") (pintype "input"))
      (node (ref "R14") (pin "2") (pinfunction "2_2") (pintype "passive"))
    )
    (net (code "15") (name "/P5V0_PGFB") (class "Default")
      (node (ref "IC11") (pin "7") (pinfunction "PGFB_7") (pintype "input"))
      (node (ref "R24") (pin "1") (pinfunction "1_1") (pintype "passive"))
      (node (ref "R30") (pin "2") (pinfunction "2_2") (pintype "passive"))
    )
    (net (code "16") (name "/P5V0_SET") (class "Default")
      (node (ref "C55") (pin "2") (pinfunction "2_2") (pintype "passive"))
      (node (ref "IC11") (pin "8") (pinfunction "SET_8") (pintype "input"))
      (node (ref "R25") (pin "2") (pinfunction "2_2") (pintype "passive"))
      (node (ref "R28") (pin "2") (pinfunction "2_2") (pintype "passive"))
    )
    (net (code "17") (name "GND") (class "Default")
      (node (ref "B10") (pin "1") (pinfunction "1_1") (pintype "bidirectional"))
      (node (ref "B11") (pin "1") (pinfunction "1_1") (pintype "bidirectional"))
      (node (ref "B9") (pin "1") (pinfunction "1_1") (pintype "bidirectional"))
      (node (ref "C15") (pin "1") (pinfunction "1_1") (pintype "passive"))
      (node (ref "C16") (pin "1") (pinfunction "1_1") (pintype "passive"))
      (node (ref "C17") (pin "1") (pinfunction "1_1") (pintype "passive"))
      (node (ref "C22") (pin "1") (pinfunction "1_1") (pintype "passive"))
      (node (ref "C23") (pin "1") (pinfunction "1_1") (pintype "passive"))
      (node (ref "C24") (pin "1") (pinfunction "1_1") (pintype "passive"))
      (node (ref "C25") (pin "1") (pinfunction "1_1") (pintype "passive"))
      (node (ref "C26") (pin "1") (pinfunction "1_1") (pintype "passive"))
      (node (ref "C27") (pin "1") (pinfunction "1_1") (pintype "passive"))
      (node (ref "C30") (pin "1") (pinfunction "1_1") (pintype "passive"))
      (node (ref "C31") (pin "1") (pinfunction "1_1") (pintype "passive"))
      (node (ref "C32") (pin "1") (pinfunction "1_1") (pintype "passive"))
      (node (ref "C33") (pin "1") (pinfunction "1_1") (pintype "passive"))
      (node (ref "C34") (pin "1") (pinfunction "1_1") (pintype "passive"))
      (node (ref "C35") (pin "1") (pinfunction "1_1") (pintype "passive"))
      (node (ref "C36") (pin "1") (pinfunction "1_1") (pintype "passive"))
      (node (ref "C37") (pin "1") (pinfunction "1_1") (pintype "passive"))
      (node (ref "C38") (pin "1") (pinfunction "1_1") (pintype "passive"))
      (node (ref "C39") (pin "1") (pinfunction "1_1") (pintype "passive"))
      (node (ref "C40") (pin "1") (pinfunction "1_1") (pintype "passive"))
      (node (ref "C41") (pin "1") (pinfunction "1_1") (pintype "passive"))
      (node (ref "C42") (pin "1") (pinfunction "1_1") (pintype "passive"))
      (node (ref "C44") (pin "1") (pinfunction "1_1") (pintype "passive"))
      (node (ref "C45") (pin "1") (pinfunction "1_1") (pintype "passive"))
      (node (ref "C46") (pin "1") (pinfunction "1_1") (pintype "passive"))
      (node (ref "C47") (pin "2") (pinfunction "2_2") (pintype "passive"))
      (node (ref "C48") (pin "1") (pinfunction "1_1") (pintype "passive"))
      (node (ref "C49") (pin "1") (pinfunction "1_1") (pintype "passive"))
      (node (ref "C50") (pin "1") (pinfunction "1_1") (pintype "passive"))
      (node (ref "C51") (pin "2") (pinfunction "2_2") (pintype "passive"))
      (node (ref "C52") (pin "1") (pinfunction "1_1") (pintype "passive"))
      (node (ref "C53") (pin "1") (pinfunction "1_1") (pintype "passive"))
      (node (ref "C54") (pin "1") (pinfunction "1_1") (pintype "passive"))
      (node (ref "C55") (pin "1") (pinfunction "1_1") (pintype "passive"))
      (node (ref "C56") (pin "1") (pinfunction "1_1") (pintype "passive"))
      (node (ref "C57") (pin "1") (pinfunction "1_1") (pintype "passive"))
      (node (ref "C58") (pin "1") (pinfunction "1_1") (pintype "passive"))
      (node (ref "C59") (pin "1") (pinfunction "1_1") (pintype "passive"))
      (node (ref "IC10") (pin "1") (pinfunction "GND_1") (pintype "power_in"))
      (node (ref "IC11") (pin "13") (pinfunction "GND_13") (pintype "power_in"))
      (node (ref "IC11") (pin "6") (pinfunction "ILIM_6") (pintype "input"))
      (node (ref "IC11") (pin "9") (pinfunction "GND_9") (pintype "power_in"))
      (node (ref "IC12") (pin "13") (pinfunction "GND_13") (pintype "power_in"))
      (node (ref "IC12") (pin "6") (pinfunction "ILIM_6") (pintype "input"))
      (node (ref "IC12") (pin "9") (pinfunction "GND_9") (pintype "power_in"))
      (node (ref "IC5") (pin "13") (pinfunction "GND_13") (pintype "power_in"))
      (node (ref "IC5") (pin "6") (pinfunction "ILIM_6") (pintype "input"))
      (node (ref "IC5") (pin "9") (pinfunction "GND_9") (pintype "power_in"))
      (node (ref "IC6") (pin "3") (pinfunction "GND_3") (pintype "power_in"))
      (node (ref "IC6") (pin "4") (pinfunction "GND_4") (pintype "power_in"))
      (node (ref "IC6") (pin "5") (pinfunction "GND_5") (pintype "power_in"))
      (node (ref "IC6") (pin "8") (pinfunction "GND_8") (pintype "power_in"))
      (node (ref "IC8") (pin "6") (pinfunction "ILIM_6") (pintype "input"))
      (node (ref "IC8") (pin "9") (pinfunction "GND_9") (pintype "power_in"))
      (node (ref "IC9") (pin "10") (pinfunction "GND_10") (pintype "power_in"))
      (node (ref "IC9") (pin "13") (pinfunction "EP_13") (pintype "power_in"))
      (node (ref "IC9") (pin "9") (pinfunction "GND_9") (pintype "power_in"))
      (node (ref "R14") (pin "1") (pinfunction "1_1") (pintype "passive"))
      (node (ref "R15") (pin "2") (pinfunction "2_2") (pintype "passive"))
      (node (ref "R17") (pin "1") (pinfunction "1_1") (pintype "passive"))
      (node (ref "R19") (pin "1") (pinfunction "1_1") (pintype "passive"))
      (node (ref "R20") (pin "1") (pinfunction "1_1") (pintype "passive"))
      (node (ref "R23") (pin "1") (pinfunction "1_1") (pintype "passive"))
      (node (ref "R25") (pin "1") (pinfunction "1_1") (pintype "passive"))
      (node (ref "R28") (pin "1") (pinfunction "1_1") (pintype "passive"))
      (node (ref "R30") (pin "1") (pinfunction "1_1") (pintype "passive"))
      (node (ref "R42") (pin "2") (pinfunction "2_2") (pintype "passive"))
      (node (ref "R44") (pin "1") (pinfunction "1_1") (pintype "passive"))
      (node (ref "R45") (pin "1") (pinfunction "1_1") (pintype "passive"))
      (node (ref "T1") (pin "2") (pinfunction "E_2") (pintype "passive"))
      (node (ref "T2") (pin "2") (pinfunction "E_2") (pintype "passive"))
    )
    (net (code "18") (name "N5V0A") (class "Default")
      (node (ref "B6") (pin "1") (pinfunction "1_1") (pintype "bidirectional"))
      (node (ref "C30") (pin "2") (pinfunction "2_2") (pintype "passive"))
      (node (ref "C33") (pin "2") (pinfunction "2_2") (pintype "passive"))
      (node (ref "L1") (pin "2") (pinfunction "2_2") (pintype "passive"))
      (node (ref "R13") (pin "2") (pinfunction "2_2") (pintype "passive"))
    )
    (net (code "19") (name "N5V5") (class "Default")
      (node (ref "C34") (pin "2") (pinfunction "2_2") (pintype "passive"))
      (node (ref "C35") (pin "2") (pinfunction "2_2") (pintype "passive"))
      (node (ref "C36") (pin "2") (pinfunction "2_2") (pintype "passive"))
      (node (ref "IC9") (pin "7") (pinfunction "VOUT_7") (pintype "input"))
      (node (ref "L2") (pin "2") (pinfunction "2_2") (pintype "passive"))
      (node (ref "L3") (pin "1") (pinfunction "1_1") (pintype "passive"))
    )
    (net (code "20") (name "N5V5_FLT") (class "Default")
      (node (ref "C37") (pin "2") (pinfunction "2_2") (pintype "passive"))
      (node (ref "C38") (pin "2") (pinfunction "2_2") (pintype "passive"))
      (node (ref "C39") (pin "2") (pinfunction "2_2") (pintype "passive"))
      (node (ref "IC8") (pin "1") (pinfunction "IN_1") (pintype "input"))
      (node (ref "IC8") (pin "13") (pinfunction "IN_13") (pintype "input"))
      (node (ref "IC8") (pin "2") (pinfunction "IN_2") (pintype "input"))
      (node (ref "L3") (pin "2") (pinfunction "2_2") (pintype "passive"))
    )
    (net (code "21") (name "Net-(IC8-PGFB)") (class "Default")
      (node (ref "IC8") (pin "5") (pinfunction "PGFB_5") (pintype "input"))
      (node (ref "R13") (pin "1") (pinfunction "1_1") (pintype "passive"))
      (node (ref "R15") (pin "1") (pinfunction "1_1") (pintype "passive"))
    )
    (net (code "22") (name "Net-(IC9-CAP)") (class "Default")
      (node (ref "C40") (pin "2") (pinfunction "2_2") (pintype "passive"))
      (node (ref "IC9") (pin "6") (pinfunction "CAP_6") (pintype "output"))
    )
    (net (code "23") (name "Net-(IC9-CP)") (class "Default")
      (node (ref "C28") (pin "2") (pinfunction "2_2") (pintype "passive"))
      (node (ref "C29") (pin "2") (pinfunction "2_2") (pintype "passive"))
      (node (ref "IC9") (pin "11") (pinfunction "CP_11") (pintype "output"))
    )
    (net (code "24") (name "Net-(IC9-FB)") (class "Default")
      (node (ref "IC9") (pin "5") (pinfunction "FB_5") (pintype "input"))
      (node (ref "R16") (pin "2") (pinfunction "2_2") (pintype "passive"))
      (node (ref "R17") (pin "2") (pinfunction "2_2") (pintype "passive"))
    )
    (net (code "25") (name "Net-(IC9-SW)") (class "Default")
      (node (ref "C28") (pin "1") (pinfunction "1_1") (pintype "passive"))
      (node (ref "C29") (pin "1") (pinfunction "1_1") (pintype "passive"))
      (node (ref "IC9") (pin "8") (pinfunction "SW_8") (pintype "output"))
      (node (ref "L2") (pin "1") (pinfunction "1_1") (pintype "passive"))
    )
    (net (code "26") (name "Net-(IC9-VAUX)") (class "Default")
      (node (ref "C41") (pin "2") (pinfunction "2_2") (pintype "passive"))
      (node (ref "IC9") (pin "1") (pinfunction "VAUX_1") (pintype "output"))
    )
    (net (code "27") (name "Net-(IC9-VREF)") (class "Default")
      (node (ref "IC9") (pin "4") (pinfunction "VREF_4") (pintype "output"))
      (node (ref "R16") (pin "1") (pinfunction "1_1") (pintype "passive"))
    )
    (net (code "28") (name "Net-(R41-Pad1)") (class "Default")
      (node (ref "R41") (pin "1") (pinfunction "1_1") (pintype "passive"))
      (node (ref "R44") (pin "2") (pinfunction "2_2") (pintype "passive"))
    )
    (net (code "29") (name "Net-(R43-Pad1)") (class "Default")
      (node (ref "R43") (pin "1") (pinfunction "1_1") (pintype "passive"))
      (node (ref "R45") (pin "2") (pinfunction "2_2") (pintype "passive"))
    )
    (net (code "30") (name "Net-(T1-B)") (class "Default")
      (node (ref "R37") (pin "1") (pinfunction "1_1") (pintype "passive"))
      (node (ref "T1") (pin "1") (pinfunction "B_1") (pintype "passive"))
    )
    (net (code "31") (name "Net-(T2-B)") (class "Default")
      (node (ref "R38") (pin "1") (pinfunction "1_1") (pintype "passive"))
      (node (ref "T2") (pin "1") (pinfunction "B_1") (pintype "passive"))
    )
    (net (code "32") (name "Net-(T2-C)") (class "Default")
      (node (ref "R35") (pin "2") (pinfunction "2_2") (pintype "passive"))
      (node (ref "R37") (pin "2") (pinfunction "2_2") (pintype "passive"))
      (node (ref "T2") (pin "3") (pinfunction "C_3") (pintype "passive"))
    )
    (net (code "33") (name "P2V0_ADC") (class "Default")
      (node (ref "B8") (pin "1") (pinfunction "1_1") (pintype "bidirectional"))
      (node (ref "C57") (pin "2") (pinfunction "2_2") (pintype "passive"))
      (node (ref "C58") (pin "2") (pinfunction "2_2") (pintype "passive"))
      (node (ref "IC12") (pin "10") (pinfunction "OUTS_10") (pintype "input"))
      (node (ref "IC12") (pin "11") (pinfunction "OUT_11") (pintype "power_in"))
      (node (ref "IC12") (pin "12") (pinfunction "OUT_12") (pintype "power_in"))
      (node (ref "R40") (pin "2") (pinfunction "2_2") (pintype "passive"))
    )
    (net (code "34") (name "P3V0_REF") (class "Default")
      (node (ref "B5") (pin "1") (pinfunction "1_1") (pintype "bidirectional"))
      (node (ref "C24") (pin "2") (pinfunction "2_2") (pintype "passive"))
      (node (ref "IC6") (pin "6") (pinfunction "VOUTS_6") (pintype "power_in"))
      (node (ref "IC6") (pin "7") (pinfunction "VOUTF_7") (pintype "power_in"))
    )
    (net (code "35") (name "P3V3_ADC") (class "Default")
      (node (ref "B4") (pin "1") (pinfunction "1_1") (pintype "bidirectional"))
      (node (ref "C16") (pin "2") (pinfunction "2_2") (pintype "passive"))
      (node (ref "C17") (pin "2") (pinfunction "2_2") (pintype "passive"))
      (node (ref "IC5") (pin "10") (pinfunction "OUTS_10") (pintype "input"))
      (node (ref "IC5") (pin "11") (pinfunction "OUT_11") (pintype "power_in"))
      (node (ref "IC5") (pin "12") (pinfunction "OUT_12") (pintype "power_in"))
      (node (ref "R39") (pin "2") (pinfunction "2_2") (pintype "passive"))
    )
    (net (code "36") (name "P5V0A") (class "Default")
      (node (ref "B7") (pin "1") (pinfunction "1_1") (pintype "bidirectional"))
      (node (ref "C23") (pin "2") (pinfunction "2_2") (pintype "passive"))
      (node (ref "C51") (pin "1") (pinfunction "1_1") (pintype "passive"))
      (node (ref "C54") (pin "2") (pinfunction "2_2") (pintype "passive"))
      (node (ref "IC6") (pin "2") (pinfunction "VIN_2") (pintype "input"))
      (node (ref "L6") (pin "2") (pinfunction "2_2") (pintype "passive"))
      (node (ref "R31") (pin "2") (pinfunction "2_2") (pintype "passive"))
    )
    (net (code "37") (name "P5V7") (class "Default")
      (node (ref "C46") (pin "2") (pinfunction "2_2") (pintype "passive"))
      (node (ref "L4") (pin "2") (pinfunction "2_2") (pintype "passive"))
      (node (ref "L5") (pin "1") (pinfunction "1_1") (pintype "passive"))
      (node (ref "R21") (pin "2") (pinfunction "2_2") (pintype "passive"))
    )
    (net (code "38") (name "P5V7_FLT") (class "Default")
      (node (ref "C15") (pin "2") (pinfunction "2_2") (pintype "passive"))
      (node (ref "C47") (pin "1") (pinfunction "1_1") (pintype "passive"))
      (node (ref "C48") (pin "2") (pinfunction "2_2") (pintype "passive"))
      (node (ref "C49") (pin "2") (pinfunction "2_2") (pintype "passive"))
      (node (ref "C50") (pin "2") (pinfunction "2_2") (pintype "passive"))
      (node (ref "C56") (pin "2") (pinfunction "2_2") (pintype "passive"))
      (node (ref "IC11") (pin "1") (pinfunction "IN_1") (pintype "input"))
      (node (ref "IC11") (pin "2") (pinfunction "IN_2") (pintype "input"))
      (node (ref "IC11") (pin "3") (pinfunction "IN_3") (pintype "input"))
      (node (ref "IC12") (pin "1") (pinfunction "IN_1") (pintype "input"))
      (node (ref "IC12") (pin "2") (pinfunction "IN_2") (pintype "input"))
      (node (ref "IC12") (pin "3") (pinfunction "IN_3") (pintype "input"))
      (node (ref "IC12") (pin "4") (pinfunction "EN/UV_4") (pintype "input"))
      (node (ref "IC5") (pin "1") (pinfunction "IN_1") (pintype "input"))
      (node (ref "IC5") (pin "2") (pinfunction "IN_2") (pintype "input"))
      (node (ref "IC5") (pin "3") (pinfunction "IN_3") (pintype "input"))
      (node (ref "L5") (pin "2") (pinfunction "2_2") (pintype "passive"))
      (node (ref "R22") (pin "2") (pinfunction "2_2") (pintype "passive"))
      (node (ref "R35") (pin "1") (pinfunction "1_1") (pintype "passive"))
      (node (ref "R36") (pin "1") (pinfunction "1_1") (pintype "passive"))
    )
    (net (code "39") (name "P12V0") (class "Default")
      (node (ref "C25") (pin "2") (pinfunction "2_2") (pintype "passive"))
      (node (ref "C26") (pin "2") (pinfunction "2_2") (pintype "passive"))
      (node (ref "C27") (pin "2") (pinfunction "2_2") (pintype "passive"))
      (node (ref "C44") (pin "2") (pinfunction "2_2") (pintype "passive"))
      (node (ref "C45") (pin "2") (pinfunction "2_2") (pintype "passive"))
      (node (ref "IC10") (pin "3") (pinfunction "VIN_3") (pintype "input"))
      (node (ref "IC9") (pin "12") (pinfunction "VIN_12") (pintype "input"))
      (node (ref "IC9") (pin "2") (pinfunction "EN_2") (pintype "input"))
    )
    (net (code "40") (name "unconnected-(IC8-VIOC-Pad7)") (class "Default")
      (node (ref "IC8") (pin "7") (pinfunction "VIOC_7") (pintype "input+no_connect"))
    )
    (net (code "41") (name "unconnected-(IC9-PG-Pad3)") (class "Default")
      (node (ref "IC9") (pin "3") (pinfunction "PG_3") (pintype "output"))
    )
    (net (code "42") (name "unconnected-(IC10-EN-Pad5)") (class "Default")
      (node (ref "IC10") (pin "5") (pinfunction "EN_5") (pintype "input+no_connect"))
    )
    (net (code "43") (name "unconnected-(IC12-PG-Pad5)") (class "Default")
      (node (ref "IC12") (pin "5") (pinfunction "PG_5") (pintype "output"))
    )
  )
)
